# LuxLogger_V2_mcu_pwr.net
KiCad netlist of a schematic drawn in Altium Designer
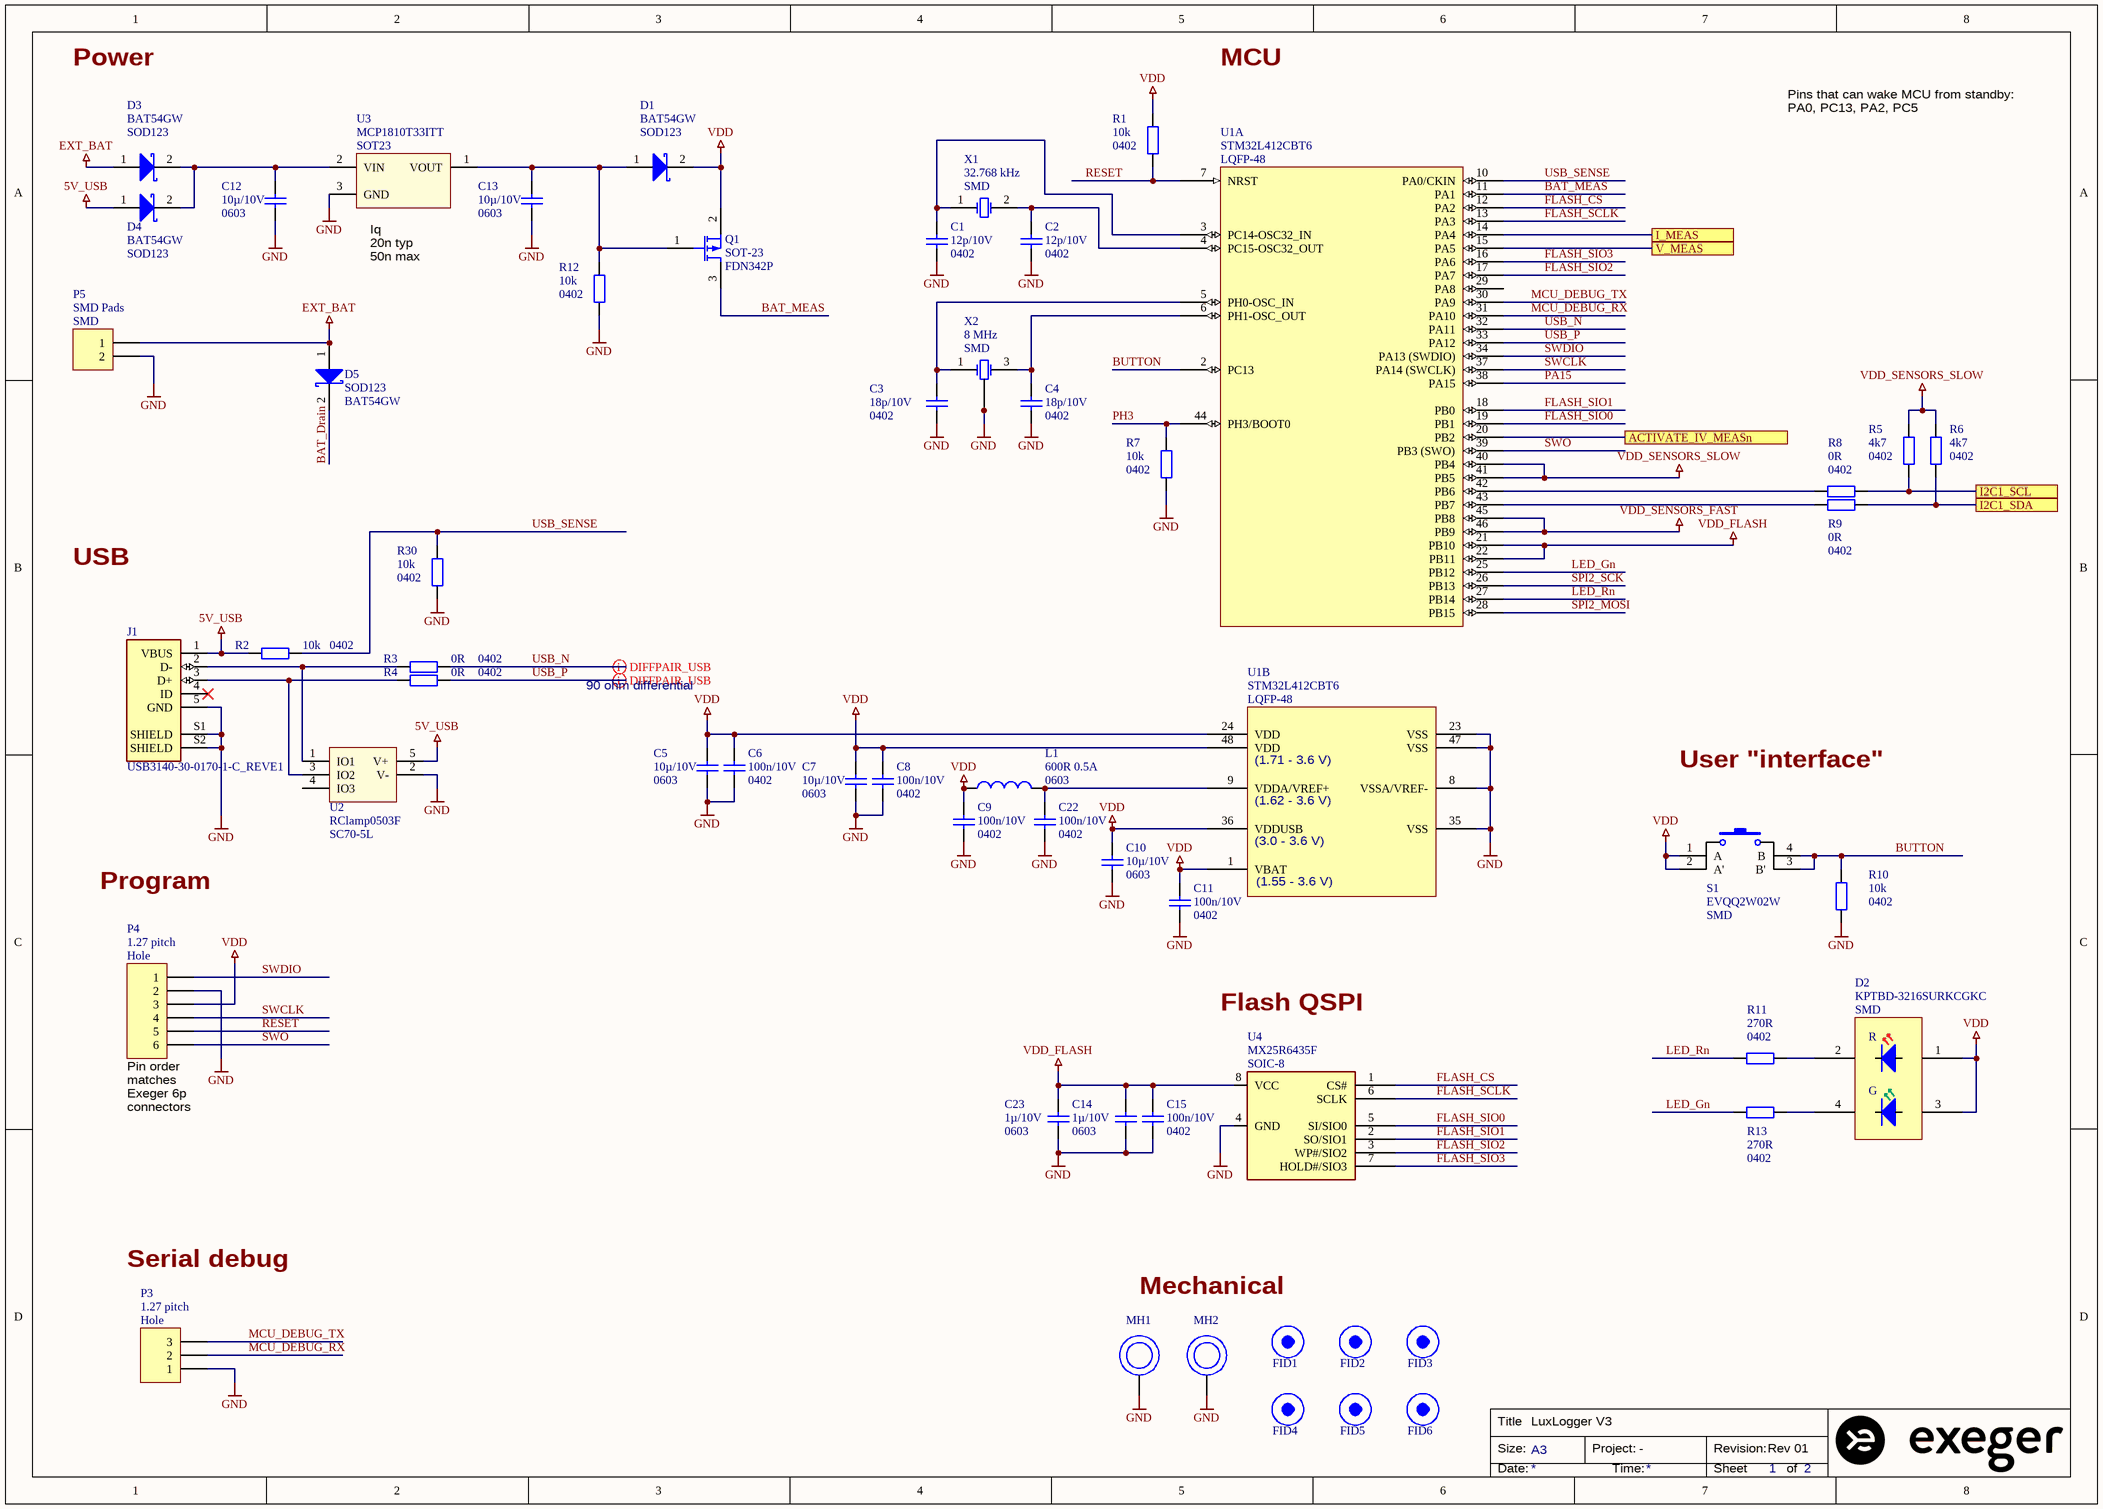
[diagram p0: LuxLogger_V2_mcu_pwr.SchDoc]

(export (version "E")
  (design (tool "Eeschema 10.0.6"))
  (components
    (comp (ref "C1")
      (value "~")
      (footprint "CAP0402")
      (description "Capacitor")
      (fields (field (name "SPECIFICATION") "12p/10V") (field (name "PACKAGE") "0402"))
      (libsource (lib "Miscellaneous Devices") (part "Cap"))
    )
    (comp (ref "C2")
      (value "~")
      (footprint "CAP0402")
      (description "Capacitor")
      (fields (field (name "SPECIFICATION") "12p/10V") (field (name "PACKAGE") "0402"))
      (libsource (lib "Miscellaneous Devices") (part "Cap"))
    )
    (comp (ref "C3")
      (value "~")
      (footprint "CAP0402")
      (description "Capacitor")
      (fields (field (name "SPECIFICATION") "18p/10V") (field (name "PACKAGE") "0402"))
      (libsource (lib "Miscellaneous Devices") (part "Cap"))
    )
    (comp (ref "C4")
      (value "~")
      (footprint "CAP0402")
      (description "Capacitor")
      (fields (field (name "SPECIFICATION") "18p/10V") (field (name "PACKAGE") "0402"))
      (libsource (lib "Miscellaneous Devices") (part "Cap"))
    )
    (comp (ref "C5")
      (value "~")
      (footprint "CAP0603")
      (description "Capacitor")
      (fields (field (name "SPECIFICATION") "10µ/10V") (field (name "PACKAGE") "0603"))
      (libsource (lib "Miscellaneous Devices") (part "Cap"))
    )
    (comp (ref "C6")
      (value "~")
      (footprint "CAP0402")
      (description "Capacitor")
      (fields (field (name "SPECIFICATION") "100n/10V") (field (name "PACKAGE") "0402"))
      (libsource (lib "Miscellaneous Devices") (part "Cap"))
    )
    (comp (ref "C7")
      (value "~")
      (footprint "CAP0603")
      (description "Capacitor")
      (fields (field (name "SPECIFICATION") "10µ/10V") (field (name "PACKAGE") "0603"))
      (libsource (lib "Miscellaneous Devices") (part "Cap"))
    )
    (comp (ref "C8")
      (value "~")
      (footprint "CAP0402")
      (description "Capacitor")
      (fields (field (name "SPECIFICATION") "100n/10V") (field (name "PACKAGE") "0402"))
      (libsource (lib "Miscellaneous Devices") (part "Cap"))
    )
    (comp (ref "C9")
      (value "~")
      (footprint "CAP0402")
      (description "Capacitor")
      (fields (field (name "SPECIFICATION") "100n/10V") (field (name "PACKAGE") "0402"))
      (libsource (lib "Miscellaneous Devices") (part "Cap"))
    )
    (comp (ref "C10")
      (value "~")
      (footprint "CAP0603")
      (description "Capacitor")
      (fields (field (name "SPECIFICATION") "10µ/10V") (field (name "PACKAGE") "0603"))
      (libsource (lib "Miscellaneous Devices") (part "Cap"))
    )
    (comp (ref "C11")
      (value "~")
      (footprint "CAP0402")
      (description "Capacitor")
      (fields (field (name "SPECIFICATION") "100n/10V") (field (name "PACKAGE") "0402"))
      (libsource (lib "Miscellaneous Devices") (part "Cap"))
    )
    (comp (ref "C12")
      (value "~")
      (footprint "CAP0603")
      (description "Capacitor")
      (fields (field (name "SPECIFICATION") "10µ/10V") (field (name "PACKAGE") "0603"))
      (libsource (lib "Miscellaneous Devices") (part "Cap"))
    )
    (comp (ref "C13")
      (value "~")
      (footprint "CAP0603")
      (description "Capacitor")
      (fields (field (name "SPECIFICATION") "10µ/10V") (field (name "PACKAGE") "0603"))
      (libsource (lib "Miscellaneous Devices") (part "Cap"))
    )
    (comp (ref "C14")
      (value "~")
      (footprint "CAP0603")
      (description "Capacitor")
      (fields (field (name "SPECIFICATION") "1µ/10V") (field (name "PACKAGE") "0603"))
      (libsource (lib "Miscellaneous Devices") (part "Cap"))
    )
    (comp (ref "C15")
      (value "~")
      (footprint "CAP0402")
      (description "Capacitor")
      (fields (field (name "SPECIFICATION") "100n/10V") (field (name "PACKAGE") "0402"))
      (libsource (lib "Miscellaneous Devices") (part "Cap"))
    )
    (comp (ref "C22")
      (value "~")
      (footprint "CAP0402")
      (description "Capacitor")
      (fields (field (name "SPECIFICATION") "100n/10V") (field (name "PACKAGE") "0402"))
      (libsource (lib "Miscellaneous Devices") (part "Cap"))
    )
    (comp (ref "C23")
      (value "~")
      (footprint "CAP0603")
      (description "Capacitor")
      (fields (field (name "SPECIFICATION") "1µ/10V") (field (name "PACKAGE") "0603"))
      (libsource (lib "Miscellaneous Devices") (part "Cap"))
    )
    (comp (ref "D1")
      (value "Alternative ON BAT54T1GOSCT-ND")
      (footprint "SOD123 SODFL360X130-2N")
      (description "Schottky Diode")
      (fields
        (field (name "MANUFACTURER") "NEXPERIA")
        (field (name "PACKAGE") "SOD123")
        (field (name "SPECIFICATION") "BAT54GW")
      )
      (libsource (lib "Exeger_schematic_library") (part "D Schottky"))
    )
    (comp (ref "D2")
      (value "~")
      (footprint "KPTBD-3216SURKCGKC")
      (description "Red/green LED")
      (fields
        (field (name "MANUFACTURER") "KINGBRIGHT")
        (field (name "PACKAGE") "SMD")
        (field (name "SPECIFICATION") "KPTBD-3216SURKCGKC")
      )
      (libsource (lib "Exeger_schematic_library") (part "LED_RG"))
    )
    (comp (ref "D3")
      (value "Alternative ON BAT54T1GOSCT-ND")
      (footprint "SOD123 SODFL360X130-2N")
      (description "Schottky Diode")
      (fields
        (field (name "MANUFACTURER") "NEXPERIA")
        (field (name "PACKAGE") "SOD123")
        (field (name "SPECIFICATION") "BAT54GW")
      )
      (libsource (lib "Exeger_schematic_library") (part "D Schottky"))
    )
    (comp (ref "D4")
      (value "Alternative ON BAT54T1GOSCT-ND")
      (footprint "SOD123 SODFL360X130-2N")
      (description "Schottky Diode")
      (fields
        (field (name "MANUFACTURER") "NEXPERIA")
        (field (name "PACKAGE") "SOD123")
        (field (name "SPECIFICATION") "BAT54GW")
      )
      (libsource (lib "Exeger_schematic_library") (part "D Schottky"))
    )
    (comp (ref "D5")
      (value "Alternative ON BAT54T1GOSCT-ND")
      (footprint "SOD123 SODFL360X130-2N")
      (description "Schottky Diode")
      (fields
        (field (name "MANUFACTURER") "NEXPERIA")
        (field (name "PACKAGE") "SOD123")
        (field (name "SPECIFICATION") "BAT54GW")
      )
      (libsource (lib "Exeger_schematic_library") (part "D Schottky"))
    )
    (comp (ref "FID1")
      (value "Fiducial")
      (footprint "FIDUCIAL_02_small")
      (libsource (lib "Exeger_schematic_library") (part "Fiducial"))
    )
    (comp (ref "FID2")
      (value "Fiducial")
      (footprint "FIDUCIAL_02_small")
      (libsource (lib "Exeger_schematic_library") (part "Fiducial"))
    )
    (comp (ref "FID3")
      (value "Fiducial")
      (footprint "FIDUCIAL_02_small")
      (libsource (lib "Exeger_schematic_library") (part "Fiducial"))
    )
    (comp (ref "FID4")
      (value "Fiducial")
      (footprint "FIDUCIAL_02_small")
      (libsource (lib "Exeger_schematic_library") (part "Fiducial"))
    )
    (comp (ref "FID5")
      (value "Fiducial")
      (footprint "FIDUCIAL_02_small")
      (libsource (lib "Exeger_schematic_library") (part "Fiducial"))
    )
    (comp (ref "FID6")
      (value "Fiducial")
      (footprint "FIDUCIAL_02_small")
      (libsource (lib "Exeger_schematic_library") (part "Fiducial"))
    )
    (comp (ref "J1")
      (value "USB3140-30-0170-1-C_REVE1")
      (footprint "GCT_USB3140-30-0170-1-C_REVE1")
      (description "USB - micro B USB 2.0 Receptacle Connector 5 Position Surface Mount, Through Hole")
      (fields (field (name "MP") "USB3140-30-0170-1-C") (field (name "MF") "Global Connector Technology"))
      (libsource (lib "USB3140-30-0170-1-C_REVE1") (part "USB3140-30-0170-1-C_REVE1"))
    )
    (comp (ref "L1")
      (value "~")
      (footprint "CAP0603")
      (description "Inductor")
      (fields
        (field (name "SPECIFICATION") "600R 0.5A")
        (field (name "PACKAGE") "0603")
        (field (name "MANUFACTURER") "MURATA")
      )
      (libsource (lib "Miscellaneous Devices") (part "Inductor"))
    )
    (comp (ref "MH1")
      (value "Mounting hole")
      (footprint "HOLE_PLATED_2300um")
      (libsource (lib "Exeger_schematic_library") (part "Mounting hole"))
    )
    (comp (ref "MH2")
      (value "Mounting hole")
      (footprint "HOLE_PLATED_2300um")
      (libsource (lib "Exeger_schematic_library") (part "Mounting hole"))
    )
    (comp (ref "P3")
      (value "~")
      (footprint "Header 1x3 1.27")
      (description "Header, 3-Pin")
      (fields (field (name "PACKAGE") "Hole") (field (name "SPECIFICATION") "1.27 pitch"))
      (libsource (lib "Miscellaneous Connectors") (part "Header 3"))
    )
    (comp (ref "P4")
      (value "~")
      (footprint "Header 1x6 1.27")
      (description "Header, 6-Pin")
      (fields (field (name "PACKAGE") "Hole") (field (name "SPECIFICATION") "1.27 pitch"))
      (libsource (lib "Miscellaneous Connectors") (part "Header 6"))
    )
    (comp (ref "P5")
      (value "~")
      (footprint "2x1 blank pads_2")
      (description "Header, 2-Pin")
      (fields (field (name "PACKAGE") "SMD") (field (name "SPECIFICATION") "SMD Pads"))
      (libsource (lib "Miscellaneous Connectors") (part "Header 2"))
    )
    (comp (ref "Q1")
      (value "~")
      (footprint "SOT23-3")
      (description "P-Channel MOSFET")
      (fields
        (field (name "MANUFACTURER") "ON")
        (field (name "PACKAGE") "SOT-23")
        (field (name "SPECIFICATION") "FDN342P")
      )
      (libsource (lib "Exeger_schematic_library") (part "MOSFET-P"))
    )
    (comp (ref "R1")
      (value "~")
      (footprint "RES0402")
      (description "Resistor")
      (fields (field (name "PACKAGE") "0402") (field (name "SPECIFICATION") "10k"))
      (libsource (lib "Miscellaneous Devices") (part "Res2"))
    )
    (comp (ref "R2")
      (value "~")
      (footprint "RES0402")
      (description "Resistor")
      (fields (field (name "PACKAGE") "0402") (field (name "SPECIFICATION") "10k"))
      (libsource (lib "") (part "Res2_1"))
    )
    (comp (ref "R3")
      (value "~")
      (footprint "RES0402")
      (description "Resistor")
      (fields (field (name "PACKAGE") "0402") (field (name "SPECIFICATION") "0R"))
      (libsource (lib "") (part "Res2_1"))
    )
    (comp (ref "R4")
      (value "~")
      (footprint "RES0402")
      (description "Resistor")
      (fields (field (name "PACKAGE") "0402") (field (name "SPECIFICATION") "0R"))
      (libsource (lib "") (part "Res2_1"))
    )
    (comp (ref "R5")
      (value "~")
      (footprint "RES0402")
      (description "Resistor")
      (fields (field (name "PACKAGE") "0402") (field (name "SPECIFICATION") "4k7"))
      (libsource (lib "Miscellaneous Devices") (part "Res2"))
    )
    (comp (ref "R6")
      (value "~")
      (footprint "RES0402")
      (description "Resistor")
      (fields (field (name "PACKAGE") "0402") (field (name "SPECIFICATION") "4k7"))
      (libsource (lib "Miscellaneous Devices") (part "Res2"))
    )
    (comp (ref "R7")
      (value "~")
      (footprint "RES0402")
      (description "Resistor")
      (fields (field (name "PACKAGE") "0402") (field (name "SPECIFICATION") "10k"))
      (libsource (lib "Miscellaneous Devices") (part "Res2"))
    )
    (comp (ref "R8")
      (value "~")
      (footprint "RES0402")
      (description "Resistor")
      (fields (field (name "PACKAGE") "0402") (field (name "SPECIFICATION") "0R"))
      (libsource (lib "") (part "Res2_1"))
    )
    (comp (ref "R9")
      (value "~")
      (footprint "RES0402")
      (description "Resistor")
      (fields (field (name "PACKAGE") "0402") (field (name "SPECIFICATION") "0R"))
      (libsource (lib "") (part "Res2_1"))
    )
    (comp (ref "R10")
      (value "~")
      (footprint "RES0402")
      (description "Resistor")
      (fields (field (name "PACKAGE") "0402") (field (name "SPECIFICATION") "10k"))
      (libsource (lib "Miscellaneous Devices") (part "Res2"))
    )
    (comp (ref "R11")
      (value "~")
      (footprint "RES0402")
      (description "Resistor")
      (fields (field (name "PACKAGE") "0402") (field (name "SPECIFICATION") "270R"))
      (libsource (lib "") (part "Res2_1"))
    )
    (comp (ref "R12")
      (value "~")
      (footprint "RES0402")
      (description "Resistor")
      (fields (field (name "PACKAGE") "0402") (field (name "SPECIFICATION") "10k"))
      (libsource (lib "Miscellaneous Devices") (part "Res2"))
    )
    (comp (ref "R13")
      (value "~")
      (footprint "RES0402")
      (description "Resistor")
      (fields (field (name "PACKAGE") "0402") (field (name "SPECIFICATION") "270R"))
      (libsource (lib "") (part "Res2_1"))
    )
    (comp (ref "R30")
      (value "~")
      (footprint "RES0402")
      (description "Resistor")
      (fields (field (name "PACKAGE") "0402") (field (name "SPECIFICATION") "10k"))
      (libsource (lib "Miscellaneous Devices") (part "Res2"))
    )
    (comp (ref "S1")
      (value "~")
      (footprint "EVQQ2W02W")
      (description "Switch")
      (fields
        (field (name "MANUFACTURER") "PANASONIC")
        (field (name "SPECIFICATION") "EVQQ2W02W")
        (field (name "PACKAGE") "SMD")
      )
      (libsource (lib "Exeger_schematic_library") (part "SW_EVQQ2"))
    )
    (comp (ref "U1")
      (value "~")
      (footprint "TSQFP50P900X900X160-48N")
      (description "MCU")
      (fields
        (field (name "SPECIFICATION") "STM32L412CBT6")
        (field (name "PACKAGE") "LQFP-48")
        (field (name "MANUFACTURER") "ST")
      )
      (libsource (lib "Exeger_schematic_library") (part "STM32L412CB_2"))
    )
    (comp (ref "U2")
      (value "~")
      (footprint "SC-70 5L")
      (description "TVS array USB")
      (fields
        (field (name "MANUFACTURER") "SEMTECH")
        (field (name "PACKAGE") "SC70-5L")
        (field (name "SPECIFICATION") "RClamp0503F")
      )
      (libsource (lib "Exeger_schematic_library") (part "RClamp0503F"))
    )
    (comp (ref "U3")
      (value "~")
      (footprint "SOT23-3")
      (description "3V3 LDO low iq")
      (fields
        (field (name "MANUFACTURER") "MICROCHIP")
        (field (name "SPECIFICATION") "MCP1810T33ITT")
        (field (name "PACKAGE") "SOT23")
      )
      (libsource (lib "Exeger_schematic_library") (part "MCP1810TxxxTT"))
    )
    (comp (ref "U4")
      (value "~")
      (footprint "SO_8_W")
      (description "ULTRA LOW POWER, 64M-BIT FLASH MEMORY")
      (fields
        (field (name "MANUFACTURER") "Macronix")
        (field (name "PACKAGE") "SOIC-8")
        (field (name "SPECIFICATION") "MX25R6435F")
      )
      (libsource (lib "Exeger_schematic_library") (part "MX25R6435F_SO8"))
    )
    (comp (ref "X1")
      (value "~")
      (footprint "FC-135")
      (description "32.768 kHz Crystal")
      (fields
        (field (name "MANUFACTURER") "EPSON")
        (field (name "PACKAGE") "SMD")
        (field (name "SPECIFICATION") "32.768 kHz")
      )
      (libsource (lib "Exeger_schematic_library") (part "XTAL 2pin"))
    )
    (comp (ref "X2")
      (value "~")
      (footprint "ABM3B")
      (description "Crystal")
      (fields
        (field (name "MANUFACTURER") "ABRACON")
        (field (name "SPECIFICATION") "8 MHz")
        (field (name "PACKAGE") "SMD")
      )
      (libsource (lib "Exeger_schematic_library") (part "XTAL 4pin"))
    )
  )
  (nets
    (net (code "1") (name "/ACTIVATE_IV_MEASn") (class "Default")
      (node (ref "U1") (pin "20") (pinfunction "PB2_20") (pintype "bidirectional"))
    )
    (net (code "2") (name "/BAT_Drain") (class "Default")
      (node (ref "D5") (pin "2") (pinfunction "K_2") (pintype "passive"))
    )
    (net (code "3") (name "/BAT_MEAS") (class "Default")
      (node (ref "Q1") (pin "3") (pinfunction "D_3") (pintype "passive"))
      (node (ref "U1") (pin "11") (pinfunction "PA1_11") (pintype "bidirectional"))
    )
    (net (code "4") (name "/BUTTON") (class "Default")
      (node (ref "R10") (pin "2") (pinfunction "2_2") (pintype "passive"))
      (node (ref "S1") (pin "3") (pinfunction "B'_3") (pintype "passive"))
      (node (ref "S1") (pin "4") (pinfunction "B_4") (pintype "passive"))
      (node (ref "U1") (pin "2") (pinfunction "PC13_2") (pintype "bidirectional"))
    )
    (net (code "5") (name "/FLASH_CS") (class "Default")
      (node (ref "U1") (pin "12") (pinfunction "PA2_12") (pintype "bidirectional"))
      (node (ref "U4") (pin "1") (pinfunction "CS#_1") (pintype "passive"))
    )
    (net (code "6") (name "/FLASH_SCLK") (class "Default")
      (node (ref "U1") (pin "13") (pinfunction "PA3_13") (pintype "bidirectional"))
      (node (ref "U4") (pin "6") (pinfunction "SCLK_6") (pintype "passive"))
    )
    (net (code "7") (name "/FLASH_SIO0") (class "Default")
      (node (ref "U1") (pin "19") (pinfunction "PB1_19") (pintype "bidirectional"))
      (node (ref "U4") (pin "5") (pinfunction "SI/SIO0_5") (pintype "passive"))
    )
    (net (code "8") (name "/FLASH_SIO1") (class "Default")
      (node (ref "U1") (pin "18") (pinfunction "PB0_18") (pintype "bidirectional"))
      (node (ref "U4") (pin "2") (pinfunction "SO/SIO1_2") (pintype "passive"))
    )
    (net (code "9") (name "/FLASH_SIO2") (class "Default")
      (node (ref "U1") (pin "17") (pinfunction "PA7_17") (pintype "bidirectional"))
      (node (ref "U4") (pin "3") (pinfunction "WP#/SIO2_3") (pintype "passive"))
    )
    (net (code "10") (name "/FLASH_SIO3") (class "Default")
      (node (ref "U1") (pin "16") (pinfunction "PA6_16") (pintype "bidirectional"))
      (node (ref "U4") (pin "7") (pinfunction "HOLD#/SIO3_7") (pintype "passive"))
    )
    (net (code "11") (name "/I2C1_SCL") (class "Default")
      (node (ref "R5") (pin "1") (pinfunction "1_1") (pintype "passive"))
      (node (ref "R8") (pin "1") (pinfunction "1_1") (pintype "passive"))
    )
    (net (code "12") (name "/I2C1_SDA") (class "Default")
      (node (ref "R6") (pin "1") (pinfunction "1_1") (pintype "passive"))
      (node (ref "R9") (pin "1") (pinfunction "1_1") (pintype "passive"))
    )
    (net (code "13") (name "/I_MEAS") (class "Default")
      (node (ref "U1") (pin "14") (pinfunction "PA4_14") (pintype "bidirectional"))
    )
    (net (code "14") (name "/LED_Gn") (class "Default")
      (node (ref "R13") (pin "2") (pinfunction "2_2") (pintype "passive"))
      (node (ref "U1") (pin "25") (pinfunction "PB12_25") (pintype "bidirectional"))
    )
    (net (code "15") (name "/LED_Rn") (class "Default")
      (node (ref "R11") (pin "2") (pinfunction "2_2") (pintype "passive"))
      (node (ref "U1") (pin "27") (pinfunction "PB14_27") (pintype "bidirectional"))
    )
    (net (code "16") (name "/MCU_DEBUG_RX") (class "Default")
      (node (ref "P3") (pin "2") (pinfunction "2_2") (pintype "passive"))
      (node (ref "U1") (pin "31") (pinfunction "PA10_31") (pintype "bidirectional"))
    )
    (net (code "17") (name "/MCU_DEBUG_TX") (class "Default")
      (node (ref "P3") (pin "3") (pinfunction "3_3") (pintype "passive"))
      (node (ref "U1") (pin "30") (pinfunction "PA9_30") (pintype "bidirectional"))
    )
    (net (code "18") (name "/PA15") (class "Default")
      (node (ref "U1") (pin "38") (pinfunction "PA15_38") (pintype "bidirectional"))
    )
    (net (code "19") (name "/PH3") (class "Default")
      (node (ref "R7") (pin "2") (pinfunction "2_2") (pintype "passive"))
      (node (ref "U1") (pin "44") (pinfunction "PH3/BOOT0_44") (pintype "bidirectional"))
    )
    (net (code "20") (name "/RESET") (class "Default")
      (node (ref "P4") (pin "5") (pinfunction "5_5") (pintype "passive"))
      (node (ref "R1") (pin "1") (pinfunction "1_1") (pintype "passive"))
      (node (ref "U1") (pin "7") (pinfunction "NRST_7") (pintype "input"))
    )
    (net (code "21") (name "/SPI2_MOSI") (class "Default")
      (node (ref "U1") (pin "28") (pinfunction "PB15_28") (pintype "bidirectional"))
    )
    (net (code "22") (name "/SPI2_SCK") (class "Default")
      (node (ref "U1") (pin "26") (pinfunction "PB13_26") (pintype "bidirectional"))
    )
    (net (code "23") (name "/SWCLK") (class "Default")
      (node (ref "P4") (pin "4") (pinfunction "4_4") (pintype "passive"))
      (node (ref "U1") (pin "37") (pinfunction "PA14_(SWCLK)_37") (pintype "bidirectional"))
    )
    (net (code "24") (name "/SWDIO") (class "Default")
      (node (ref "P4") (pin "1") (pinfunction "1_1") (pintype "passive"))
      (node (ref "U1") (pin "34") (pinfunction "PA13_(SWDIO)_34") (pintype "bidirectional"))
    )
    (net (code "25") (name "/SWO") (class "Default")
      (node (ref "P4") (pin "6") (pinfunction "6_6") (pintype "passive"))
      (node (ref "U1") (pin "39") (pinfunction "PB3_(SWO)_39") (pintype "bidirectional"))
    )
    (net (code "26") (name "/USB_N") (class "Default")
      (node (ref "R3") (pin "1") (pinfunction "1_1") (pintype "passive"))
      (node (ref "U1") (pin "32") (pinfunction "PA11_32") (pintype "bidirectional"))
    )
    (net (code "27") (name "/USB_P") (class "Default")
      (node (ref "R4") (pin "1") (pinfunction "1_1") (pintype "passive"))
      (node (ref "U1") (pin "33") (pinfunction "PA12_33") (pintype "bidirectional"))
    )
    (net (code "28") (name "/USB_SENSE") (class "Default")
      (node (ref "R2") (pin "1") (pinfunction "1_1") (pintype "passive"))
      (node (ref "R30") (pin "2") (pinfunction "2_2") (pintype "passive"))
      (node (ref "U1") (pin "10") (pinfunction "PA0/CKIN_10") (pintype "bidirectional"))
    )
    (net (code "29") (name "/V_MEAS") (class "Default")
      (node (ref "U1") (pin "15") (pinfunction "PA5_15") (pintype "bidirectional"))
    )
    (net (code "30") (name "5V_USB") (class "Default")
      (node (ref "D4") (pin "1") (pinfunction "A_1") (pintype "passive"))
      (node (ref "J1") (pin "1") (pinfunction "VBUS_1") (pintype "power_in"))
      (node (ref "R2") (pin "2") (pinfunction "2_2") (pintype "passive"))
      (node (ref "U2") (pin "5") (pinfunction "V+_5") (pintype "power_in"))
    )
    (net (code "31") (name "EXT_BAT") (class "Default")
      (node (ref "D3") (pin "1") (pinfunction "A_1") (pintype "passive"))
      (node (ref "D5") (pin "1") (pinfunction "A_1") (pintype "passive"))
      (node (ref "P5") (pin "1") (pinfunction "1_1") (pintype "passive"))
    )
    (net (code "32") (name "GND") (class "Default")
      (node (ref "C1") (pin "1") (pinfunction "1_1") (pintype "passive"))
      (node (ref "C10") (pin "1") (pinfunction "1_1") (pintype "passive"))
      (node (ref "C11") (pin "1") (pinfunction "1_1") (pintype "passive"))
      (node (ref "C12") (pin "1") (pinfunction "1_1") (pintype "passive"))
      (node (ref "C13") (pin "1") (pinfunction "1_1") (pintype "passive"))
      (node (ref "C14") (pin "1") (pinfunction "1_1") (pintype "passive"))
      (node (ref "C15") (pin "1") (pinfunction "1_1") (pintype "passive"))
      (node (ref "C2") (pin "1") (pinfunction "1_1") (pintype "passive"))
      (node (ref "C22") (pin "1") (pinfunction "1_1") (pintype "passive"))
      (node (ref "C23") (pin "1") (pinfunction "1_1") (pintype "passive"))
      (node (ref "C3") (pin "1") (pinfunction "1_1") (pintype "passive"))
      (node (ref "C4") (pin "1") (pinfunction "1_1") (pintype "passive"))
      (node (ref "C5") (pin "1") (pinfunction "1_1") (pintype "passive"))
      (node (ref "C6") (pin "1") (pinfunction "1_1") (pintype "passive"))
      (node (ref "C7") (pin "1") (pinfunction "1_1") (pintype "passive"))
      (node (ref "C8") (pin "1") (pinfunction "1_1") (pintype "passive"))
      (node (ref "C9") (pin "1") (pinfunction "1_1") (pintype "passive"))
      (node (ref "J1") (pin "5") (pinfunction "GND_5") (pintype "power_in"))
      (node (ref "J1") (pin "S1") (pinfunction "SHIELD_S1") (pintype "passive"))
      (node (ref "J1") (pin "S2") (pinfunction "SHIELD_S2") (pintype "passive"))
      (node (ref "MH1") (pin "1") (pinfunction "1_1") (pintype "passive"))
      (node (ref "MH2") (pin "1") (pinfunction "1_1") (pintype "passive"))
      (node (ref "P3") (pin "1") (pinfunction "1_1") (pintype "passive"))
      (node (ref "P4") (pin "2") (pinfunction "2_2") (pintype "passive"))
      (node (ref "P5") (pin "2") (pinfunction "2_2") (pintype "passive"))
      (node (ref "R10") (pin "1") (pinfunction "1_1") (pintype "passive"))
      (node (ref "R12") (pin "1") (pinfunction "1_1") (pintype "passive"))
      (node (ref "R30") (pin "1") (pinfunction "1_1") (pintype "passive"))
      (node (ref "R7") (pin "1") (pinfunction "1_1") (pintype "passive"))
      (node (ref "U1") (pin "23") (pinfunction "VSS_23") (pintype "power_in"))
      (node (ref "U1") (pin "35") (pinfunction "VSS_35") (pintype "power_in"))
      (node (ref "U1") (pin "47") (pinfunction "VSS_47") (pintype "power_in"))
      (node (ref "U1") (pin "8") (pinfunction "VSSA/VREF-_8") (pintype "power_in"))
      (node (ref "U2") (pin "2") (pinfunction "V-_2") (pintype "power_in"))
      (node (ref "U3") (pin "3") (pinfunction "GND_3") (pintype "power_in"))
      (node (ref "U4") (pin "4") (pinfunction "GND_4") (pintype "passive"))
      (node (ref "X2") (pin "2") (pinfunction "GND_2") (pintype "passive"))
      (node (ref "X2") (pin "4") (pinfunction "GND_4") (pintype "passive"))
    )
    (net (code "33") (name "Net-(D1-A)") (class "Default")
      (node (ref "C13") (pin "2") (pinfunction "2_2") (pintype "passive"))
      (node (ref "D1") (pin "1") (pinfunction "A_1") (pintype "passive"))
      (node (ref "Q1") (pin "1") (pinfunction "G_1") (pintype "passive"))
      (node (ref "R12") (pin "2") (pinfunction "2_2") (pintype "passive"))
      (node (ref "U3") (pin "1") (pinfunction "VOUT_1") (pintype "power_in"))
    )
    (net (code "34") (name "Net-(D2-G_K)") (class "Default")
      (node (ref "D2") (pin "4") (pinfunction "G_K_4") (pintype "passive"))
      (node (ref "R13") (pin "1") (pinfunction "1_1") (pintype "passive"))
    )
    (net (code "35") (name "Net-(D2-R_K)") (class "Default")
      (node (ref "D2") (pin "2") (pinfunction "R_K_2") (pintype "passive"))
      (node (ref "R11") (pin "1") (pinfunction "1_1") (pintype "passive"))
    )
    (net (code "36") (name "Net-(D3-K)") (class "Default")
      (node (ref "C12") (pin "2") (pinfunction "2_2") (pintype "passive"))
      (node (ref "D3") (pin "2") (pinfunction "K_2") (pintype "passive"))
      (node (ref "D4") (pin "2") (pinfunction "K_2") (pintype "passive"))
      (node (ref "U3") (pin "2") (pinfunction "VIN_2") (pintype "passive"))
    )
    (net (code "37") (name "Net-(J1-D+)") (class "Default")
      (node (ref "J1") (pin "3") (pinfunction "D+_3") (pintype "bidirectional"))
      (node (ref "R4") (pin "2") (pinfunction "2_2") (pintype "passive"))
      (node (ref "U2") (pin "3") (pinfunction "IO2_3") (pintype "power_in"))
    )
    (net (code "38") (name "Net-(J1-D-)") (class "Default")
      (node (ref "J1") (pin "2") (pinfunction "D-_2") (pintype "bidirectional"))
      (node (ref "R3") (pin "2") (pinfunction "2_2") (pintype "passive"))
      (node (ref "U2") (pin "1") (pinfunction "IO1_1") (pintype "power_in"))
    )
    (net (code "39") (name "Net-(U1A-PB6)") (class "Default")
      (node (ref "R8") (pin "2") (pinfunction "2_2") (pintype "passive"))
      (node (ref "U1") (pin "42") (pinfunction "PB6_42") (pintype "bidirectional"))
    )
    (net (code "40") (name "Net-(U1A-PB7)") (class "Default")
      (node (ref "R9") (pin "2") (pinfunction "2_2") (pintype "passive"))
      (node (ref "U1") (pin "43") (pinfunction "PB7_43") (pintype "bidirectional"))
    )
    (net (code "41") (name "Net-(U1A-PC14-OSC32_IN)") (class "Default")
      (node (ref "C1") (pin "2") (pinfunction "2_2") (pintype "passive"))
      (node (ref "U1") (pin "3") (pinfunction "PC14-OSC32_IN_3") (pintype "bidirectional"))
      (node (ref "X1") (pin "1") (pinfunction "OSC1_1") (pintype "passive"))
    )
    (net (code "42") (name "Net-(U1A-PC15-OSC32_OUT)") (class "Default")
      (node (ref "C2") (pin "2") (pinfunction "2_2") (pintype "passive"))
      (node (ref "U1") (pin "4") (pinfunction "PC15-OSC32_OUT_4") (pintype "bidirectional"))
      (node (ref "X1") (pin "2") (pinfunction "OSC2_2") (pintype "passive"))
    )
    (net (code "43") (name "Net-(U1A-PH0-OSC_IN)") (class "Default")
      (node (ref "C3") (pin "2") (pinfunction "2_2") (pintype "passive"))
      (node (ref "U1") (pin "5") (pinfunction "PH0-OSC_IN_5") (pintype "bidirectional"))
      (node (ref "X2") (pin "1") (pinfunction "OSC1_1") (pintype "passive"))
    )
    (net (code "44") (name "Net-(U1A-PH1-OSC_OUT)") (class "Default")
      (node (ref "C4") (pin "2") (pinfunction "2_2") (pintype "passive"))
      (node (ref "U1") (pin "6") (pinfunction "PH1-OSC_OUT_6") (pintype "bidirectional"))
      (node (ref "X2") (pin "3") (pinfunction "OSC2_3") (pintype "passive"))
    )
    (net (code "45") (name "Net-(U1B-VDDA{slash}VREF+)") (class "Default")
      (node (ref "C22") (pin "2") (pinfunction "2_2") (pintype "passive"))
      (node (ref "L1") (pin "2") (pinfunction "2_2") (pintype "passive"))
      (node (ref "U1") (pin "9") (pinfunction "VDDA/VREF+_9") (pintype "power_in"))
    )
    (net (code "46") (name "VDD") (class "Default")
      (node (ref "C10") (pin "2") (pinfunction "2_2") (pintype "passive"))
      (node (ref "C11") (pin "2") (pinfunction "2_2") (pintype "passive"))
      (node (ref "C5") (pin "2") (pinfunction "2_2") (pintype "passive"))
      (node (ref "C6") (pin "2") (pinfunction "2_2") (pintype "passive"))
      (node (ref "C7") (pin "2") (pinfunction "2_2") (pintype "passive"))
      (node (ref "C8") (pin "2") (pinfunction "2_2") (pintype "passive"))
      (node (ref "C9") (pin "2") (pinfunction "2_2") (pintype "passive"))
      (node (ref "D1") (pin "2") (pinfunction "K_2") (pintype "passive"))
      (node (ref "D2") (pin "1") (pinfunction "R_A_1") (pintype "passive"))
      (node (ref "D2") (pin "3") (pinfunction "G_A_3") (pintype "passive"))
      (node (ref "L1") (pin "1") (pinfunction "1_1") (pintype "passive"))
      (node (ref "P4") (pin "3") (pinfunction "3_3") (pintype "passive"))
      (node (ref "Q1") (pin "2") (pinfunction "S_2") (pintype "passive"))
      (node (ref "R1") (pin "2") (pinfunction "2_2") (pintype "passive"))
      (node (ref "S1") (pin "1") (pinfunction "A_1") (pintype "passive"))
      (node (ref "S1") (pin "2") (pinfunction "A'_2") (pintype "passive"))
      (node (ref "U1") (pin "1") (pinfunction "VBAT_1") (pintype "power_in"))
      (node (ref "U1") (pin "24") (pinfunction "VDD_24") (pintype "power_in"))
      (node (ref "U1") (pin "36") (pinfunction "VDDUSB_36") (pintype "power_in"))
      (node (ref "U1") (pin "48") (pinfunction "VDD_48") (pintype "power_in"))
    )
    (net (code "47") (name "VDD_FLASH") (class "Default")
      (node (ref "C14") (pin "2") (pinfunction "2_2") (pintype "passive"))
      (node (ref "C15") (pin "2") (pinfunction "2_2") (pintype "passive"))
      (node (ref "C23") (pin "2") (pinfunction "2_2") (pintype "passive"))
      (node (ref "U1") (pin "21") (pinfunction "PB10_21") (pintype "bidirectional"))
      (node (ref "U1") (pin "22") (pinfunction "PB11_22") (pintype "bidirectional"))
      (node (ref "U4") (pin "8") (pinfunction "VCC_8") (pintype "passive"))
    )
    (net (code "48") (name "VDD_SENSORS_FAST") (class "Default")
      (node (ref "U1") (pin "45") (pinfunction "PB8_45") (pintype "bidirectional"))
      (node (ref "U1") (pin "46") (pinfunction "PB9_46") (pintype "bidirectional"))
    )
    (net (code "49") (name "VDD_SENSORS_SLOW") (class "Default")
      (node (ref "R5") (pin "2") (pinfunction "2_2") (pintype "passive"))
      (node (ref "R6") (pin "2") (pinfunction "2_2") (pintype "passive"))
      (node (ref "U1") (pin "40") (pinfunction "PB4_40") (pintype "bidirectional"))
      (node (ref "U1") (pin "41") (pinfunction "PB5_41") (pintype "bidirectional"))
    )
    (net (code "50") (name "unconnected-(J1-ID-Pad4)") (class "Default")
      (node (ref "J1") (pin "4") (pinfunction "ID_4") (pintype "passive+no_connect"))
    )
    (net (code "51") (name "unconnected-(U1A-PA8-Pad29)") (class "Default")
      (node (ref "U1") (pin "29") (pinfunction "PA8_29") (pintype "bidirectional"))
    )
    (net (code "52") (name "unconnected-(U2-IO3-Pad4)") (class "Default")
      (node (ref "U2") (pin "4") (pinfunction "IO3_4") (pintype "power_in"))
    )
  )
)
